# ChildBoard.net
KiCad netlist of a schematic drawn in Altium Designer
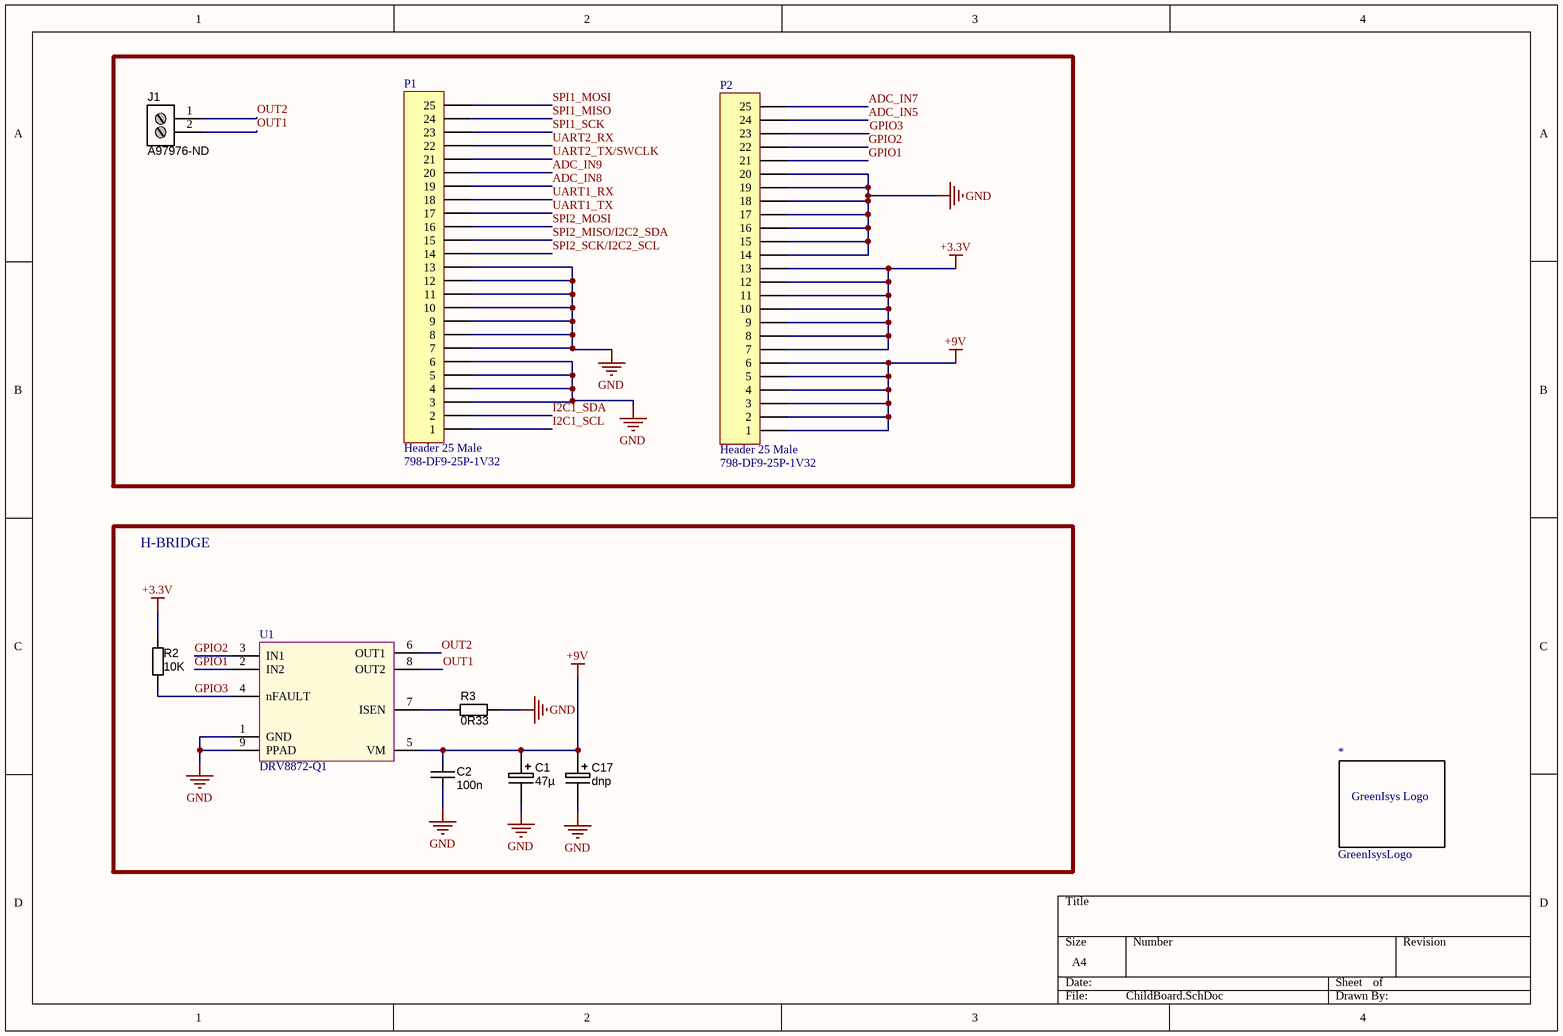
[diagram p0: ChildBoard.SchDoc]

(export (version "E")
  (design (tool "Eeschema 10.0.6"))
  (components
    (comp (ref "*")
      (value "GreenIsysLogo")
      (footprint "GreenIsys")
      (libsource (lib "ruben_schematic") (part "GreenIsysLogo"))
    )
    (comp (ref "C1")
      (value "47µ")
      (footprint "CAP_ELEC_Size_H13")
      (description "Capacitor SMD Electrolytic 47uF 20% 100V Radial")
      (fields (field (name "TOLERANCE") "±20%"))
      (libsource (lib "PBL - Capacitors") (part "CAPE_47u_100V_SMD"))
    )
    (comp (ref "C2")
      (value "100n")
      (footprint "CAPC1608N")
      (description "Capacitor SMD Cer 100nF 10% 10V X7R 0603")
      (fields (field (name "TOLERANCE") "±10%") (field (name "Comment") "approved sub OK"))
      (libsource (lib "PBL - Capacitors") (part "CAPC_10n_0603_50V_10%"))
    )
    (comp (ref "C17")
      (value "dnp")
      (footprint "CAPMP3528X210N")
      (description "Capacitor SMD Tantalum 47uF 10% 6.3V EIA 3528-21")
      (fields (field (name "TOLERANCE") "±10%"))
      (libsource (lib "PBL - Capacitors") (part "CAPT_47u_3528_6V3"))
    )
    (comp (ref "J1")
      (value "Stackable ScrewTerm")
      (footprint "2P_PCB_ScrewTerm_90S_3.81MM")
      (description "Terminal Block Screw Type THT 2-Position 3.81mm pitch")
      (fields (field (name "SUPPLIER PART NUMBER 1") "A97976-ND"))
      (libsource (lib "PBL - Connectors") (part "2P_ScrewTerm_90S_3.81MM"))
    )
    (comp (ref "P1")
      (value "Header 25 Male")
      (footprint "DF9-25S-1V (MALE)")
      (description "Header, 25-Pin")
      (fields
        (field (name "SUPPLIER PART NUMBER 1") "798-DF9-25P-1V32")
        (field (name "PUBLISHER") "Altium Limited")
      )
      (libsource (lib "MainBoardSch") (part "Header 25 Male"))
    )
    (comp (ref "P2")
      (value "Header 25 Male")
      (footprint "DF9-25S-1V (MALE)")
      (description "Header, 25-Pin")
      (fields
        (field (name "SUPPLIER PART NUMBER 1") "798-DF9-25P-1V32")
        (field (name "PUBLISHER") "Altium Limited")
      )
      (libsource (lib "MainBoardSch") (part "Header 25 Male"))
    )
    (comp (ref "R2")
      (value "10K")
      (footprint "RESC1608N")
      (description "Resistor SMD chip 10k Ohm 0.1W 1% 0603")
      (fields (field (name "TOLERANCE") "±1%") (field (name "Comment") "Thick Film"))
      (libsource (lib "PBL - Resistors") (part "RES_10K_0603_1%"))
    )
    (comp (ref "R3")
      (value "0R33")
      (footprint "RESC3225N")
      (description "Resistor SMD chip 0.33 Ohm 0.5W 1% 1210")
      (fields (field (name "TOLERANCE") "±1%") (field (name "Comment") "Thick Film"))
      (libsource (lib "PBL - Resistors") (part "RES_2R2_1210_5%"))
    )
    (comp (ref "U1")
      (value "DRV8872-Q1")
      (footprint "HSOP-8-DDA")
      (libsource (lib "ruben_schematic") (part "DRV8872-Q1"))
    )
  )
  (nets
    (net (code "1") (name "+3.3V") (class "Default")
      (node (ref "P2") (pin "10") (pinfunction "10_10") (pintype "passive"))
      (node (ref "P2") (pin "11") (pinfunction "11_11") (pintype "passive"))
      (node (ref "P2") (pin "12") (pinfunction "12_12") (pintype "passive"))
      (node (ref "P2") (pin "13") (pinfunction "13_13") (pintype "passive"))
      (node (ref "P2") (pin "7") (pinfunction "7_7") (pintype "passive"))
      (node (ref "P2") (pin "8") (pinfunction "8_8") (pintype "passive"))
      (node (ref "P2") (pin "9") (pinfunction "9_9") (pintype "passive"))
      (node (ref "R2") (pin "1") (pinfunction "1_1") (pintype "passive"))
    )
    (net (code "2") (name "+9V") (class "Default")
      (node (ref "C1") (pin "1") (pintype "passive"))
      (node (ref "C17") (pin "1") (pintype "passive"))
      (node (ref "C2") (pin "1") (pintype "passive"))
      (node (ref "P2") (pin "1") (pinfunction "1_1") (pintype "passive"))
      (node (ref "P2") (pin "2") (pinfunction "2_2") (pintype "passive"))
      (node (ref "P2") (pin "3") (pinfunction "3_3") (pintype "passive"))
      (node (ref "P2") (pin "4") (pinfunction "4_4") (pintype "passive"))
      (node (ref "P2") (pin "5") (pinfunction "5_5") (pintype "passive"))
      (node (ref "P2") (pin "6") (pinfunction "6_6") (pintype "passive"))
      (node (ref "U1") (pin "5") (pinfunction "VM_5") (pintype "passive"))
    )
    (net (code "3") (name "/ADC_IN5") (class "Default")
      (node (ref "P2") (pin "24") (pinfunction "24_24") (pintype "passive"))
    )
    (net (code "4") (name "/ADC_IN7") (class "Default")
      (node (ref "P2") (pin "25") (pinfunction "25_25") (pintype "passive"))
    )
    (net (code "5") (name "/ADC_IN8") (class "Default")
      (node (ref "P1") (pin "19") (pinfunction "19_19") (pintype "passive"))
    )
    (net (code "6") (name "/ADC_IN9") (class "Default")
      (node (ref "P1") (pin "20") (pinfunction "20_20") (pintype "passive"))
    )
    (net (code "7") (name "/GPIO1") (class "Default")
      (node (ref "P2") (pin "21") (pinfunction "21_21") (pintype "passive"))
      (node (ref "U1") (pin "2") (pinfunction "IN2_2") (pintype "passive"))
    )
    (net (code "8") (name "/GPIO2") (class "Default")
      (node (ref "P2") (pin "22") (pinfunction "22_22") (pintype "passive"))
      (node (ref "U1") (pin "3") (pinfunction "IN1_3") (pintype "passive"))
    )
    (net (code "9") (name "/GPIO3") (class "Default")
      (node (ref "P2") (pin "23") (pinfunction "23_23") (pintype "passive"))
      (node (ref "R2") (pin "2") (pinfunction "2_2") (pintype "passive"))
      (node (ref "U1") (pin "4") (pinfunction "nFAULT_4") (pintype "passive"))
    )
    (net (code "10") (name "/I2C1_SCL") (class "Default")
      (node (ref "P1") (pin "1") (pinfunction "1_1") (pintype "passive"))
    )
    (net (code "11") (name "/I2C1_SDA") (class "Default")
      (node (ref "P1") (pin "2") (pinfunction "2_2") (pintype "passive"))
    )
    (net (code "12") (name "/OUT1") (class "Default")
      (node (ref "J1") (pin "2") (pinfunction "2_2") (pintype "passive"))
      (node (ref "U1") (pin "8") (pinfunction "OUT2_8") (pintype "passive"))
    )
    (net (code "13") (name "/OUT2") (class "Default")
      (node (ref "J1") (pin "1") (pinfunction "1_1") (pintype "passive"))
      (node (ref "U1") (pin "6") (pinfunction "OUT1_6") (pintype "passive"))
    )
    (net (code "14") (name "/SPI1_MISO") (class "Default")
      (node (ref "P1") (pin "24") (pinfunction "24_24") (pintype "passive"))
    )
    (net (code "15") (name "/SPI1_MOSI") (class "Default")
      (node (ref "P1") (pin "25") (pinfunction "25_25") (pintype "passive"))
    )
    (net (code "16") (name "/SPI1_SCK") (class "Default")
      (node (ref "P1") (pin "23") (pinfunction "23_23") (pintype "passive"))
    )
    (net (code "17") (name "/SPI2_MISO{slash}I2C2_SDA") (class "Default")
      (node (ref "P1") (pin "15") (pinfunction "15_15") (pintype "passive"))
    )
    (net (code "18") (name "/SPI2_MOSI") (class "Default")
      (node (ref "P1") (pin "16") (pinfunction "16_16") (pintype "passive"))
    )
    (net (code "19") (name "/SPI2_SCK{slash}I2C2_SCL") (class "Default")
      (node (ref "P1") (pin "14") (pinfunction "14_14") (pintype "passive"))
    )
    (net (code "20") (name "/UART1_RX") (class "Default")
      (node (ref "P1") (pin "18") (pinfunction "18_18") (pintype "passive"))
    )
    (net (code "21") (name "/UART1_TX") (class "Default")
      (node (ref "P1") (pin "17") (pinfunction "17_17") (pintype "passive"))
    )
    (net (code "22") (name "/UART2_RX") (class "Default")
      (node (ref "P1") (pin "22") (pinfunction "22_22") (pintype "passive"))
    )
    (net (code "23") (name "/UART2_TX{slash}SWCLK") (class "Default")
      (node (ref "P1") (pin "21") (pinfunction "21_21") (pintype "passive"))
    )
    (net (code "24") (name "GND") (class "Default")
      (node (ref "C1") (pin "2") (pintype "passive"))
      (node (ref "C17") (pin "2") (pintype "passive"))
      (node (ref "C2") (pin "2") (pintype "passive"))
      (node (ref "P1") (pin "10") (pinfunction "10_10") (pintype "passive"))
      (node (ref "P1") (pin "11") (pinfunction "11_11") (pintype "passive"))
      (node (ref "P1") (pin "12") (pinfunction "12_12") (pintype "passive"))
      (node (ref "P1") (pin "13") (pinfunction "13_13") (pintype "passive"))
      (node (ref "P1") (pin "3") (pinfunction "3_3") (pintype "passive"))
      (node (ref "P1") (pin "4") (pinfunction "4_4") (pintype "passive"))
      (node (ref "P1") (pin "5") (pinfunction "5_5") (pintype "passive"))
      (node (ref "P1") (pin "6") (pinfunction "6_6") (pintype "passive"))
      (node (ref "P1") (pin "7") (pinfunction "7_7") (pintype "passive"))
      (node (ref "P1") (pin "8") (pinfunction "8_8") (pintype "passive"))
      (node (ref "P1") (pin "9") (pinfunction "9_9") (pintype "passive"))
      (node (ref "P2") (pin "14") (pinfunction "14_14") (pintype "passive"))
      (node (ref "P2") (pin "15") (pinfunction "15_15") (pintype "passive"))
      (node (ref "P2") (pin "16") (pinfunction "16_16") (pintype "passive"))
      (node (ref "P2") (pin "17") (pinfunction "17_17") (pintype "passive"))
      (node (ref "P2") (pin "18") (pinfunction "18_18") (pintype "passive"))
      (node (ref "P2") (pin "19") (pinfunction "19_19") (pintype "passive"))
      (node (ref "P2") (pin "20") (pinfunction "20_20") (pintype "passive"))
      (node (ref "R3") (pin "1") (pinfunction "1_1") (pintype "passive"))
      (node (ref "U1") (pin "1") (pinfunction "GND_1") (pintype "passive"))
      (node (ref "U1") (pin "9") (pinfunction "PPAD_9") (pintype "passive"))
    )
    (net (code "25") (name "Net-(U1-ISEN)") (class "Default")
      (node (ref "R3") (pin "2") (pinfunction "2_2") (pintype "passive"))
      (node (ref "U1") (pin "7") (pinfunction "ISEN_7") (pintype "passive"))
    )
  )
)
